# AD9851.net
KiCad netlist of a schematic drawn in Altium Designer
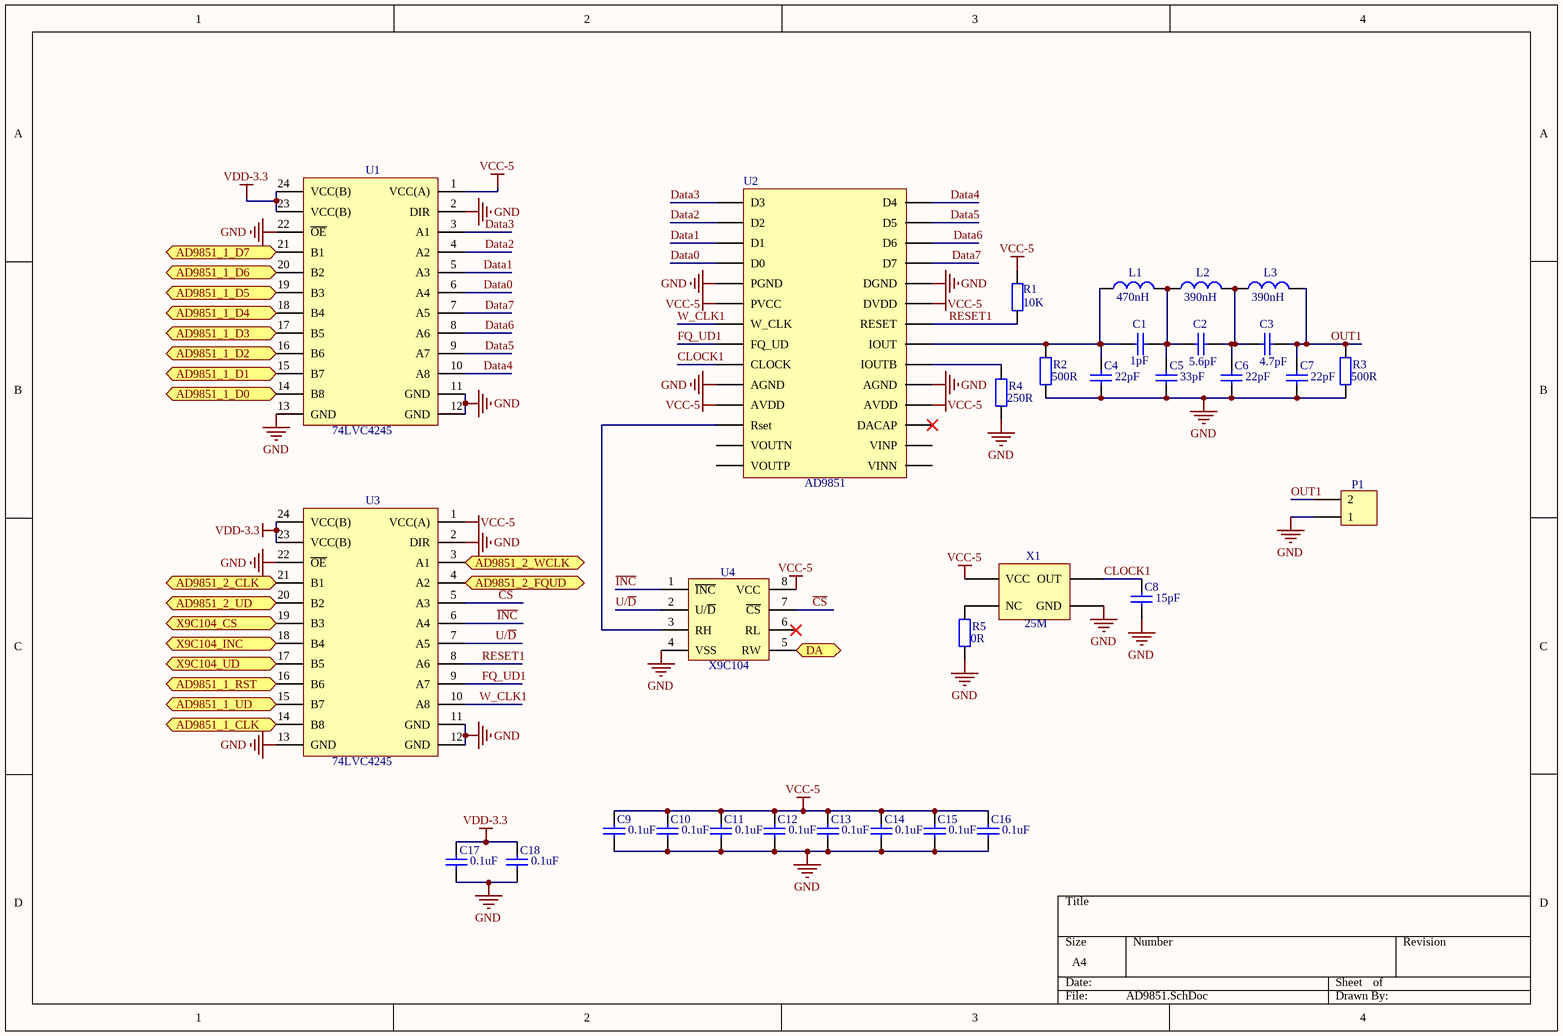
[diagram p0: AD9851.SchDoc]

(export (version "E")
  (design (tool "Eeschema 10.0.6"))
  (components
    (comp (ref "C1")
      (value "1pF")
      (footprint "0603")
      (fields (field (name "Comment") "Capacitor-0603"))
      (libsource (lib "原理图库") (part "Capacitor-0603"))
    )
    (comp (ref "C2")
      (value "5.6pF")
      (footprint "0603")
      (fields (field (name "Comment") "Capacitor-0603"))
      (libsource (lib "原理图库") (part "Capacitor-0603"))
    )
    (comp (ref "C3")
      (value "4.7pF")
      (footprint "0603")
      (fields (field (name "Comment") "Capacitor-0603"))
      (libsource (lib "原理图库") (part "Capacitor-0603"))
    )
    (comp (ref "C4")
      (value "22pF")
      (footprint "0603")
      (fields (field (name "Comment") "Capacitor-0603"))
      (libsource (lib "原理图库") (part "Capacitor-0603"))
    )
    (comp (ref "C5")
      (value "33pF")
      (footprint "0603")
      (fields (field (name "Comment") "Capacitor-0603"))
      (libsource (lib "原理图库") (part "Capacitor-0603"))
    )
    (comp (ref "C6")
      (value "22pF")
      (footprint "0603")
      (fields (field (name "Comment") "Capacitor-0603"))
      (libsource (lib "原理图库") (part "Capacitor-0603"))
    )
    (comp (ref "C7")
      (value "22pF")
      (footprint "0603")
      (fields (field (name "Comment") "Capacitor-0603"))
      (libsource (lib "原理图库") (part "Capacitor-0603"))
    )
    (comp (ref "C8")
      (value "15pF")
      (footprint "0603")
      (fields (field (name "Comment") "Capacitor-0603"))
      (libsource (lib "原理图库") (part "Capacitor-0603"))
    )
    (comp (ref "C9")
      (value "0.1uF")
      (footprint "0603")
      (fields (field (name "Comment") "Capacitor-0603"))
      (libsource (lib "原理图库") (part "Capacitor-0603"))
    )
    (comp (ref "C10")
      (value "0.1uF")
      (footprint "0603")
      (fields (field (name "Comment") "Capacitor-0603"))
      (libsource (lib "原理图库") (part "Capacitor-0603"))
    )
    (comp (ref "C11")
      (value "0.1uF")
      (footprint "0603")
      (fields (field (name "Comment") "Capacitor-0603"))
      (libsource (lib "原理图库") (part "Capacitor-0603"))
    )
    (comp (ref "C12")
      (value "0.1uF")
      (footprint "0603")
      (fields (field (name "Comment") "Capacitor-0603"))
      (libsource (lib "原理图库") (part "Capacitor-0603"))
    )
    (comp (ref "C13")
      (value "0.1uF")
      (footprint "0603")
      (fields (field (name "Comment") "Capacitor-0603"))
      (libsource (lib "原理图库") (part "Capacitor-0603"))
    )
    (comp (ref "C14")
      (value "0.1uF")
      (footprint "0603")
      (fields (field (name "Comment") "Capacitor-0603"))
      (libsource (lib "原理图库") (part "Capacitor-0603"))
    )
    (comp (ref "C15")
      (value "0.1uF")
      (footprint "0603")
      (fields (field (name "Comment") "Capacitor-0603"))
      (libsource (lib "原理图库") (part "Capacitor-0603"))
    )
    (comp (ref "C16")
      (value "0.1uF")
      (footprint "0603")
      (fields (field (name "Comment") "Capacitor-0603"))
      (libsource (lib "原理图库") (part "Capacitor-0603"))
    )
    (comp (ref "C17")
      (value "0.1uF")
      (footprint "0603")
      (fields (field (name "Comment") "Capacitor-0603"))
      (libsource (lib "原理图库") (part "Capacitor-0603"))
    )
    (comp (ref "C18")
      (value "0.1uF")
      (footprint "0603")
      (fields (field (name "Comment") "Capacitor-0603"))
      (libsource (lib "原理图库") (part "Capacitor-0603"))
    )
    (comp (ref "L1")
      (value "470nH")
      (footprint "0805")
      (fields (field (name "Comment") "Inductor"))
      (libsource (lib "原理图库") (part "Inductor"))
    )
    (comp (ref "L2")
      (value "390nH")
      (footprint "0805")
      (fields (field (name "Comment") "Inductor"))
      (libsource (lib "原理图库") (part "Inductor"))
    )
    (comp (ref "L3")
      (value "390nH")
      (footprint "0805")
      (fields (field (name "Comment") "Inductor"))
      (libsource (lib "原理图库") (part "Inductor"))
    )
    (comp (ref "P1") (value "端子") (footprint "2MM接线端子") (libsource (lib "原理图库") (part "端子")))
    (comp (ref "R1")
      (value "10K")
      (footprint "0603")
      (fields (field (name "Comment") "Resistor-0603"))
      (libsource (lib "原理图库") (part "Resistor-0603"))
    )
    (comp (ref "R2")
      (value "500R")
      (footprint "0603")
      (fields (field (name "Comment") "Resistor-0603"))
      (libsource (lib "原理图库") (part "Resistor-0603"))
    )
    (comp (ref "R3")
      (value "500R")
      (footprint "0603")
      (fields (field (name "Comment") "Resistor-0603"))
      (libsource (lib "原理图库") (part "Resistor-0603"))
    )
    (comp (ref "R4")
      (value "250R")
      (footprint "0603")
      (fields (field (name "Comment") "Resistor-0603"))
      (libsource (lib "原理图库") (part "Resistor-0603"))
    )
    (comp (ref "R5")
      (value "0R")
      (footprint "0603")
      (fields (field (name "Comment") "Resistor-0603"))
      (libsource (lib "原理图库") (part "Resistor-0603"))
    )
    (comp (ref "U1")
      (value "74LVC4245")
      (footprint "74LVC4245-PW")
      (fields (field (name "NAME") "74LVC4245"))
      (libsource (lib "原理图库") (part "74LVC4245"))
    )
    (comp (ref "U2")
      (value "AD9851")
      (footprint "AD9851")
      (fields (field (name "NAME") "AD9851"))
      (libsource (lib "原理图库") (part "AD9851"))
    )
    (comp (ref "U3")
      (value "74LVC4245")
      (footprint "74LVC4245-PW")
      (fields (field (name "NAME") "74LVC4245"))
      (libsource (lib "原理图库") (part "74LVC4245"))
    )
    (comp (ref "U4")
      (value "X9C104数字电位器")
      (footprint "X9C104")
      (fields (field (name "NAME") "X9C104"))
      (libsource (lib "原理图库") (part "X9C104数字电位器"))
    )
    (comp (ref "X1")
      (value "25M")
      (footprint "有源晶振7050")
      (fields (field (name "Comment") "有源晶振"))
      (libsource (lib "原理图库") (part "有源晶振"))
    )
  )
  (nets
    (net (code "1") (name "/AD9851_1_CLK") (class "Default")
      (node (ref "U3") (pin "14") (pinfunction "B8_14") (pintype "passive"))
    )
    (net (code "2") (name "/AD9851_1_D0") (class "Default")
      (node (ref "U1") (pin "14") (pinfunction "B8_14") (pintype "passive"))
    )
    (net (code "3") (name "/AD9851_1_D1") (class "Default")
      (node (ref "U1") (pin "15") (pinfunction "B7_15") (pintype "passive"))
    )
    (net (code "4") (name "/AD9851_1_D2") (class "Default")
      (node (ref "U1") (pin "16") (pinfunction "B6_16") (pintype "passive"))
    )
    (net (code "5") (name "/AD9851_1_D3") (class "Default")
      (node (ref "U1") (pin "17") (pinfunction "B5_17") (pintype "passive"))
    )
    (net (code "6") (name "/AD9851_1_D4") (class "Default")
      (node (ref "U1") (pin "18") (pinfunction "B4_18") (pintype "passive"))
    )
    (net (code "7") (name "/AD9851_1_D5") (class "Default")
      (node (ref "U1") (pin "19") (pinfunction "B3_19") (pintype "passive"))
    )
    (net (code "8") (name "/AD9851_1_D6") (class "Default")
      (node (ref "U1") (pin "20") (pinfunction "B2_20") (pintype "passive"))
    )
    (net (code "9") (name "/AD9851_1_D7") (class "Default")
      (node (ref "U1") (pin "21") (pinfunction "B1_21") (pintype "passive"))
    )
    (net (code "10") (name "/AD9851_1_RST") (class "Default")
      (node (ref "U3") (pin "16") (pinfunction "B6_16") (pintype "passive"))
    )
    (net (code "11") (name "/AD9851_1_UD") (class "Default")
      (node (ref "U3") (pin "15") (pinfunction "B7_15") (pintype "passive"))
    )
    (net (code "12") (name "/AD9851_2_CLK") (class "Default")
      (node (ref "U3") (pin "21") (pinfunction "B1_21") (pintype "passive"))
    )
    (net (code "13") (name "/AD9851_2_FQUD") (class "Default")
      (node (ref "U3") (pin "4") (pinfunction "A2_4") (pintype "passive"))
    )
    (net (code "14") (name "/AD9851_2_UD") (class "Default")
      (node (ref "U3") (pin "20") (pinfunction "B2_20") (pintype "passive"))
    )
    (net (code "15") (name "/AD9851_2_WCLK") (class "Default")
      (node (ref "U3") (pin "3") (pinfunction "A1_3") (pintype "passive"))
    )
    (net (code "16") (name "/CLOCK1") (class "Default")
      (node (ref "C8") (pin "2") (pinfunction "2_2") (pintype "passive"))
      (node (ref "U2") (pin "9") (pinfunction "CLOCK_9") (pintype "passive"))
      (node (ref "X1") (pin "3") (pinfunction "OUT_3") (pintype "passive"))
    )
    (net (code "17") (name "/DA") (class "Default")
      (node (ref "U4") (pin "5") (pinfunction "RW_5") (pintype "passive"))
    )
    (net (code "18") (name "/Data0") (class "Default")
      (node (ref "U1") (pin "6") (pinfunction "A4_6") (pintype "passive"))
      (node (ref "U2") (pin "4") (pinfunction "D0_4") (pintype "passive"))
    )
    (net (code "19") (name "/Data1") (class "Default")
      (node (ref "U1") (pin "5") (pinfunction "A3_5") (pintype "passive"))
      (node (ref "U2") (pin "3") (pinfunction "D1_3") (pintype "passive"))
    )
    (net (code "20") (name "/Data2") (class "Default")
      (node (ref "U1") (pin "4") (pinfunction "A2_4") (pintype "passive"))
      (node (ref "U2") (pin "2") (pinfunction "D2_2") (pintype "passive"))
    )
    (net (code "21") (name "/Data3") (class "Default")
      (node (ref "U1") (pin "3") (pinfunction "A1_3") (pintype "passive"))
      (node (ref "U2") (pin "1") (pinfunction "D3_1") (pintype "passive"))
    )
    (net (code "22") (name "/Data4") (class "Default")
      (node (ref "U1") (pin "10") (pinfunction "A8_10") (pintype "passive"))
      (node (ref "U2") (pin "28") (pinfunction "D4_28") (pintype "passive"))
    )
    (net (code "23") (name "/Data5") (class "Default")
      (node (ref "U1") (pin "9") (pinfunction "A7_9") (pintype "passive"))
      (node (ref "U2") (pin "27") (pinfunction "D5_27") (pintype "passive"))
    )
    (net (code "24") (name "/Data6") (class "Default")
      (node (ref "U1") (pin "8") (pinfunction "A6_8") (pintype "passive"))
      (node (ref "U2") (pin "26") (pinfunction "D6_26") (pintype "passive"))
    )
    (net (code "25") (name "/Data7") (class "Default")
      (node (ref "U1") (pin "7") (pinfunction "A5_7") (pintype "passive"))
      (node (ref "U2") (pin "25") (pinfunction "D7_25") (pintype "passive"))
    )
    (net (code "26") (name "/FQ_UD1") (class "Default")
      (node (ref "U2") (pin "8") (pinfunction "FQ_UD_8") (pintype "passive"))
      (node (ref "U3") (pin "9") (pinfunction "A7_9") (pintype "passive"))
    )
    (net (code "27") (name "/OUT1") (class "Default")
      (node (ref "C3") (pin "1") (pinfunction "1_1") (pintype "passive"))
      (node (ref "C7") (pin "2") (pinfunction "2_2") (pintype "passive"))
      (node (ref "L3") (pin "2") (pinfunction "2_2") (pintype "passive"))
      (node (ref "P1") (pin "2") (pinfunction "2_2") (pintype "passive"))
      (node (ref "R3") (pin "2") (pinfunction "2_2") (pintype "passive"))
    )
    (net (code "28") (name "/RESET1") (class "Default")
      (node (ref "R1") (pin "1") (pinfunction "1_1") (pintype "passive"))
      (node (ref "U2") (pin "22") (pinfunction "RESET_22") (pintype "passive"))
      (node (ref "U3") (pin "8") (pinfunction "A6_8") (pintype "passive"))
    )
    (net (code "29") (name "/U{slash}~{D}") (class "Default")
      (node (ref "U3") (pin "7") (pinfunction "A5_7") (pintype "passive"))
      (node (ref "U4") (pin "2") (pinfunction "U/~{D}_2") (pintype "passive"))
    )
    (net (code "30") (name "/W_CLK1") (class "Default")
      (node (ref "U2") (pin "7") (pinfunction "W_CLK_7") (pintype "passive"))
      (node (ref "U3") (pin "10") (pinfunction "A8_10") (pintype "passive"))
    )
    (net (code "31") (name "/X9C104_CS") (class "Default")
      (node (ref "U3") (pin "19") (pinfunction "B3_19") (pintype "passive"))
    )
    (net (code "32") (name "/X9C104_INC") (class "Default")
      (node (ref "U3") (pin "18") (pinfunction "B4_18") (pintype "passive"))
    )
    (net (code "33") (name "/X9C104_UD") (class "Default")
      (node (ref "U3") (pin "17") (pinfunction "B5_17") (pintype "passive"))
    )
    (net (code "34") (name "/~{CS}") (class "Default")
      (node (ref "U3") (pin "5") (pinfunction "A3_5") (pintype "passive"))
      (node (ref "U4") (pin "7") (pinfunction "~{CS}_7") (pintype "passive"))
    )
    (net (code "35") (name "/~{INC}") (class "Default")
      (node (ref "U3") (pin "6") (pinfunction "A4_6") (pintype "passive"))
      (node (ref "U4") (pin "1") (pinfunction "~{INC}_1") (pintype "passive"))
    )
    (net (code "36") (name "GND") (class "Default")
      (node (ref "C10") (pin "1") (pinfunction "1_1") (pintype "passive"))
      (node (ref "C11") (pin "1") (pinfunction "1_1") (pintype "passive"))
      (node (ref "C12") (pin "1") (pinfunction "1_1") (pintype "passive"))
      (node (ref "C13") (pin "1") (pinfunction "1_1") (pintype "passive"))
      (node (ref "C14") (pin "1") (pinfunction "1_1") (pintype "passive"))
      (node (ref "C15") (pin "1") (pinfunction "1_1") (pintype "passive"))
      (node (ref "C16") (pin "1") (pinfunction "1_1") (pintype "passive"))
      (node (ref "C17") (pin "1") (pinfunction "1_1") (pintype "passive"))
      (node (ref "C18") (pin "1") (pinfunction "1_1") (pintype "passive"))
      (node (ref "C4") (pin "1") (pinfunction "1_1") (pintype "passive"))
      (node (ref "C5") (pin "1") (pinfunction "1_1") (pintype "passive"))
      (node (ref "C6") (pin "1") (pinfunction "1_1") (pintype "passive"))
      (node (ref "C7") (pin "1") (pinfunction "1_1") (pintype "passive"))
      (node (ref "C8") (pin "1") (pinfunction "1_1") (pintype "passive"))
      (node (ref "C9") (pin "1") (pinfunction "1_1") (pintype "passive"))
      (node (ref "P1") (pin "1") (pinfunction "1_1") (pintype "passive"))
      (node (ref "R2") (pin "1") (pinfunction "1_1") (pintype "passive"))
      (node (ref "R3") (pin "1") (pinfunction "1_1") (pintype "passive"))
      (node (ref "R4") (pin "1") (pinfunction "1_1") (pintype "passive"))
      (node (ref "R5") (pin "1") (pinfunction "1_1") (pintype "passive"))
      (node (ref "U1") (pin "11") (pinfunction "GND_11") (pintype "passive"))
      (node (ref "U1") (pin "12") (pinfunction "GND_12") (pintype "passive"))
      (node (ref "U1") (pin "13") (pinfunction "GND_13") (pintype "passive"))
      (node (ref "U1") (pin "2") (pinfunction "DIR_2") (pintype "passive"))
      (node (ref "U1") (pin "22") (pinfunction "~{OE}_22") (pintype "passive"))
      (node (ref "U2") (pin "10") (pinfunction "AGND_10") (pintype "passive"))
      (node (ref "U2") (pin "19") (pinfunction "AGND_19") (pintype "passive"))
      (node (ref "U2") (pin "24") (pinfunction "DGND_24") (pintype "passive"))
      (node (ref "U2") (pin "5") (pinfunction "PGND_5") (pintype "passive"))
      (node (ref "U3") (pin "11") (pinfunction "GND_11") (pintype "passive"))
      (node (ref "U3") (pin "12") (pinfunction "GND_12") (pintype "passive"))
      (node (ref "U3") (pin "13") (pinfunction "GND_13") (pintype "passive"))
      (node (ref "U3") (pin "2") (pinfunction "DIR_2") (pintype "passive"))
      (node (ref "U3") (pin "22") (pinfunction "~{OE}_22") (pintype "passive"))
      (node (ref "U4") (pin "4") (pinfunction "VSS_4") (pintype "passive"))
      (node (ref "X1") (pin "2") (pinfunction "GND_2") (pintype "passive"))
    )
    (net (code "37") (name "Net-(C1-Pad1)") (class "Default")
      (node (ref "C1") (pin "1") (pinfunction "1_1") (pintype "passive"))
      (node (ref "C2") (pin "2") (pinfunction "2_2") (pintype "passive"))
      (node (ref "C5") (pin "2") (pinfunction "2_2") (pintype "passive"))
      (node (ref "L1") (pin "2") (pinfunction "2_2") (pintype "passive"))
      (node (ref "L2") (pin "1") (pinfunction "1_1") (pintype "passive"))
    )
    (net (code "38") (name "Net-(C2-Pad1)") (class "Default")
      (node (ref "C2") (pin "1") (pinfunction "1_1") (pintype "passive"))
      (node (ref "C3") (pin "2") (pinfunction "2_2") (pintype "passive"))
      (node (ref "C6") (pin "2") (pinfunction "2_2") (pintype "passive"))
      (node (ref "L2") (pin "2") (pinfunction "2_2") (pintype "passive"))
      (node (ref "L3") (pin "1") (pinfunction "1_1") (pintype "passive"))
    )
    (net (code "39") (name "Net-(U2-IOUT)") (class "Default")
      (node (ref "C1") (pin "2") (pinfunction "2_2") (pintype "passive"))
      (node (ref "C4") (pin "2") (pinfunction "2_2") (pintype "passive"))
      (node (ref "L1") (pin "1") (pinfunction "1_1") (pintype "passive"))
      (node (ref "R2") (pin "2") (pinfunction "2_2") (pintype "passive"))
      (node (ref "U2") (pin "21") (pinfunction "IOUT_21") (pintype "passive"))
    )
    (net (code "40") (name "Net-(U2-IOUTB)") (class "Default")
      (node (ref "R4") (pin "2") (pinfunction "2_2") (pintype "passive"))
      (node (ref "U2") (pin "20") (pinfunction "IOUTB_20") (pintype "passive"))
    )
    (net (code "41") (name "Net-(U2-Rset)") (class "Default")
      (node (ref "U2") (pin "12") (pinfunction "Rset_12") (pintype "passive"))
      (node (ref "U4") (pin "3") (pinfunction "RH_3") (pintype "passive"))
    )
    (net (code "42") (name "Net-(X1-NC)") (class "Default")
      (node (ref "R5") (pin "2") (pinfunction "2_2") (pintype "passive"))
      (node (ref "X1") (pin "1") (pinfunction "NC_1") (pintype "passive"))
    )
    (net (code "43") (name "VCC-5") (class "Default")
      (node (ref "C10") (pin "2") (pinfunction "2_2") (pintype "passive"))
      (node (ref "C11") (pin "2") (pinfunction "2_2") (pintype "passive"))
      (node (ref "C12") (pin "2") (pinfunction "2_2") (pintype "passive"))
      (node (ref "C13") (pin "2") (pinfunction "2_2") (pintype "passive"))
      (node (ref "C14") (pin "2") (pinfunction "2_2") (pintype "passive"))
      (node (ref "C15") (pin "2") (pinfunction "2_2") (pintype "passive"))
      (node (ref "C16") (pin "2") (pinfunction "2_2") (pintype "passive"))
      (node (ref "C9") (pin "2") (pinfunction "2_2") (pintype "passive"))
      (node (ref "R1") (pin "2") (pinfunction "2_2") (pintype "passive"))
      (node (ref "U1") (pin "1") (pinfunction "VCC(A)_1") (pintype "passive"))
      (node (ref "U2") (pin "11") (pinfunction "AVDD_11") (pintype "passive"))
      (node (ref "U2") (pin "18") (pinfunction "AVDD_18") (pintype "passive"))
      (node (ref "U2") (pin "23") (pinfunction "DVDD_23") (pintype "passive"))
      (node (ref "U2") (pin "6") (pinfunction "PVCC_6") (pintype "passive"))
      (node (ref "U3") (pin "1") (pinfunction "VCC(A)_1") (pintype "passive"))
      (node (ref "U4") (pin "8") (pinfunction "VCC_8") (pintype "passive"))
      (node (ref "X1") (pin "4") (pinfunction "VCC_4") (pintype "passive"))
    )
    (net (code "44") (name "VDD-3.3") (class "Default")
      (node (ref "C17") (pin "2") (pinfunction "2_2") (pintype "passive"))
      (node (ref "C18") (pin "2") (pinfunction "2_2") (pintype "passive"))
      (node (ref "U1") (pin "23") (pinfunction "VCC(B)_23") (pintype "passive"))
      (node (ref "U1") (pin "24") (pinfunction "VCC(B)_24") (pintype "passive"))
      (node (ref "U3") (pin "23") (pinfunction "VCC(B)_23") (pintype "passive"))
      (node (ref "U3") (pin "24") (pinfunction "VCC(B)_24") (pintype "passive"))
    )
    (net (code "45") (name "unconnected-(U2-DACAP-Pad17)") (class "Default")
      (node (ref "U2") (pin "17") (pinfunction "DACAP_17") (pintype "passive+no_connect"))
    )
    (net (code "46") (name "unconnected-(U2-VINN-Pad15)") (class "Default")
      (node (ref "U2") (pin "15") (pinfunction "VINN_15") (pintype "passive"))
    )
    (net (code "47") (name "unconnected-(U2-VINP-Pad16)") (class "Default")
      (node (ref "U2") (pin "16") (pinfunction "VINP_16") (pintype "passive"))
    )
    (net (code "48") (name "unconnected-(U2-VOUTN-Pad13)") (class "Default")
      (node (ref "U2") (pin "13") (pinfunction "VOUTN_13") (pintype "passive"))
    )
    (net (code "49") (name "unconnected-(U2-VOUTP-Pad14)") (class "Default")
      (node (ref "U2") (pin "14") (pinfunction "VOUTP_14") (pintype "passive"))
    )
    (net (code "50") (name "unconnected-(U4-RL-Pad6)") (class "Default")
      (node (ref "U4") (pin "6") (pinfunction "RL_6") (pintype "passive+no_connect"))
    )
  )
)
